# Sheet1.net
KiCad netlist of a schematic drawn in Altium Designer
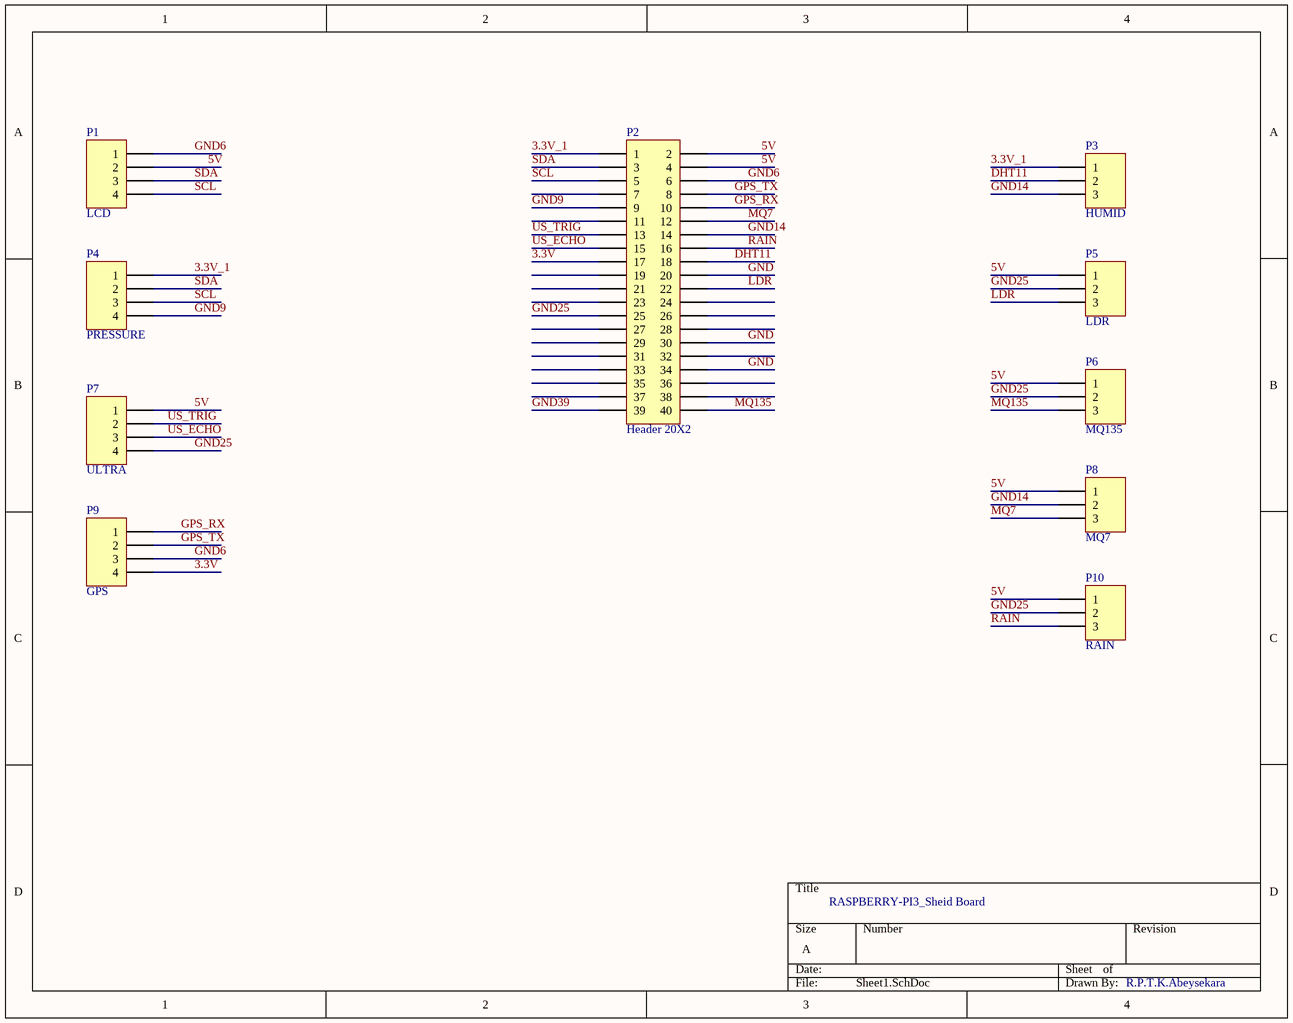
[diagram p0: Sheet1.SchDoc]

(export (version "E")
  (design (tool "Eeschema 10.0.6"))
  (components
    (comp (ref "P1")
      (value "LCD")
      (footprint "HDR1X4")
      (description "Header, 4-Pin")
      (fields (field (name "PUBLISHER") "Altium Limited"))
      (libsource (lib "Miscellaneous Connectors") (part "Header 4"))
    )
    (comp (ref "P2")
      (value "Header 20X2")
      (footprint "HDR2X20")
      (description "Header, 20-Pin, Dual row")
      (fields (field (name "PUBLISHER") "Altium Limited"))
      (libsource (lib "Miscellaneous Connectors") (part "Header 20X2"))
    )
    (comp (ref "P3")
      (value "HUMID")
      (footprint "HDR1X3")
      (description "Header, 3-Pin")
      (fields (field (name "PUBLISHER") "Altium Limited"))
      (libsource (lib "Miscellaneous Connectors") (part "Header 3"))
    )
    (comp (ref "P4")
      (value "PRESSURE")
      (footprint "HDR1X4")
      (description "Header, 4-Pin")
      (fields (field (name "PUBLISHER") "Altium Limited"))
      (libsource (lib "Miscellaneous Connectors") (part "Header 4"))
    )
    (comp (ref "P5")
      (value "LDR")
      (footprint "HDR1X3")
      (description "Header, 3-Pin")
      (fields (field (name "PUBLISHER") "Altium Limited"))
      (libsource (lib "Miscellaneous Connectors") (part "Header 3"))
    )
    (comp (ref "P6")
      (value "MQ135")
      (footprint "HDR1X3")
      (description "Header, 3-Pin")
      (fields (field (name "PUBLISHER") "Altium Limited"))
      (libsource (lib "Miscellaneous Connectors") (part "Header 3"))
    )
    (comp (ref "P7")
      (value "ULTRA")
      (footprint "HDR1X4")
      (description "Header, 4-Pin")
      (fields (field (name "PUBLISHER") "Altium Limited"))
      (libsource (lib "Miscellaneous Connectors") (part "Header 4"))
    )
    (comp (ref "P8")
      (value "MQ7")
      (footprint "HDR1X3")
      (description "Header, 3-Pin")
      (fields (field (name "PUBLISHER") "Altium Limited"))
      (libsource (lib "Miscellaneous Connectors") (part "Header 3"))
    )
    (comp (ref "P9")
      (value "GPS")
      (footprint "HDR1X4")
      (description "Header, 4-Pin")
      (fields (field (name "PUBLISHER") "Altium Limited"))
      (libsource (lib "Miscellaneous Connectors") (part "Header 4"))
    )
    (comp (ref "P10")
      (value "RAIN")
      (footprint "HDR1X3")
      (description "Header, 3-Pin")
      (fields (field (name "PUBLISHER") "Altium Limited"))
      (libsource (lib "Miscellaneous Connectors") (part "Header 3"))
    )
  )
  (nets
    (net (code "1") (name "/3.3V") (class "Default")
      (node (ref "P2") (pin "17") (pinfunction "17_17") (pintype "passive"))
      (node (ref "P9") (pin "4") (pinfunction "4_4") (pintype "passive"))
    )
    (net (code "2") (name "/3.3V_1") (class "Default")
      (node (ref "P2") (pin "1") (pinfunction "1_1") (pintype "passive"))
      (node (ref "P3") (pin "1") (pinfunction "1_1") (pintype "passive"))
      (node (ref "P4") (pin "1") (pinfunction "1_1") (pintype "passive"))
    )
    (net (code "3") (name "/5V") (class "Default")
      (node (ref "P1") (pin "2") (pinfunction "2_2") (pintype "passive"))
      (node (ref "P10") (pin "1") (pinfunction "1_1") (pintype "passive"))
      (node (ref "P2") (pin "2") (pinfunction "2_2") (pintype "passive"))
      (node (ref "P2") (pin "4") (pinfunction "4_4") (pintype "passive"))
      (node (ref "P5") (pin "1") (pinfunction "1_1") (pintype "passive"))
      (node (ref "P6") (pin "1") (pinfunction "1_1") (pintype "passive"))
      (node (ref "P7") (pin "1") (pinfunction "1_1") (pintype "passive"))
      (node (ref "P8") (pin "1") (pinfunction "1_1") (pintype "passive"))
    )
    (net (code "4") (name "/DHT11") (class "Default")
      (node (ref "P2") (pin "18") (pinfunction "18_18") (pintype "passive"))
      (node (ref "P3") (pin "2") (pinfunction "2_2") (pintype "passive"))
    )
    (net (code "5") (name "/GND") (class "Default")
      (node (ref "P2") (pin "20") (pinfunction "20_20") (pintype "passive"))
      (node (ref "P2") (pin "30") (pinfunction "30_30") (pintype "passive"))
      (node (ref "P2") (pin "34") (pinfunction "34_34") (pintype "passive"))
    )
    (net (code "6") (name "/GND6") (class "Default")
      (node (ref "P1") (pin "1") (pinfunction "1_1") (pintype "passive"))
      (node (ref "P2") (pin "6") (pinfunction "6_6") (pintype "passive"))
      (node (ref "P9") (pin "3") (pinfunction "3_3") (pintype "passive"))
    )
    (net (code "7") (name "/GND9") (class "Default")
      (node (ref "P2") (pin "9") (pinfunction "9_9") (pintype "passive"))
      (node (ref "P4") (pin "4") (pinfunction "4_4") (pintype "passive"))
    )
    (net (code "8") (name "/GND14") (class "Default")
      (node (ref "P2") (pin "14") (pinfunction "14_14") (pintype "passive"))
      (node (ref "P3") (pin "3") (pinfunction "3_3") (pintype "passive"))
      (node (ref "P8") (pin "2") (pinfunction "2_2") (pintype "passive"))
    )
    (net (code "9") (name "/GND25") (class "Default")
      (node (ref "P10") (pin "2") (pinfunction "2_2") (pintype "passive"))
      (node (ref "P2") (pin "25") (pinfunction "25_25") (pintype "passive"))
      (node (ref "P5") (pin "2") (pinfunction "2_2") (pintype "passive"))
      (node (ref "P6") (pin "2") (pinfunction "2_2") (pintype "passive"))
      (node (ref "P7") (pin "4") (pinfunction "4_4") (pintype "passive"))
    )
    (net (code "10") (name "/GND39") (class "Default")
      (node (ref "P2") (pin "39") (pinfunction "39_39") (pintype "passive"))
    )
    (net (code "11") (name "/GPS_RX") (class "Default")
      (node (ref "P2") (pin "10") (pinfunction "10_10") (pintype "passive"))
      (node (ref "P9") (pin "1") (pinfunction "1_1") (pintype "passive"))
    )
    (net (code "12") (name "/GPS_TX") (class "Default")
      (node (ref "P2") (pin "8") (pinfunction "8_8") (pintype "passive"))
      (node (ref "P9") (pin "2") (pinfunction "2_2") (pintype "passive"))
    )
    (net (code "13") (name "/LDR") (class "Default")
      (node (ref "P2") (pin "22") (pinfunction "22_22") (pintype "passive"))
      (node (ref "P5") (pin "3") (pinfunction "3_3") (pintype "passive"))
    )
    (net (code "14") (name "/MQ7") (class "Default")
      (node (ref "P2") (pin "12") (pinfunction "12_12") (pintype "passive"))
      (node (ref "P8") (pin "3") (pinfunction "3_3") (pintype "passive"))
    )
    (net (code "15") (name "/MQ135") (class "Default")
      (node (ref "P2") (pin "40") (pinfunction "40_40") (pintype "passive"))
      (node (ref "P6") (pin "3") (pinfunction "3_3") (pintype "passive"))
    )
    (net (code "16") (name "/RAIN") (class "Default")
      (node (ref "P10") (pin "3") (pinfunction "3_3") (pintype "passive"))
      (node (ref "P2") (pin "16") (pinfunction "16_16") (pintype "passive"))
    )
    (net (code "17") (name "/SCL") (class "Default")
      (node (ref "P1") (pin "4") (pinfunction "4_4") (pintype "passive"))
      (node (ref "P2") (pin "5") (pinfunction "5_5") (pintype "passive"))
      (node (ref "P4") (pin "3") (pinfunction "3_3") (pintype "passive"))
    )
    (net (code "18") (name "/SDA") (class "Default")
      (node (ref "P1") (pin "3") (pinfunction "3_3") (pintype "passive"))
      (node (ref "P2") (pin "3") (pinfunction "3_3") (pintype "passive"))
      (node (ref "P4") (pin "2") (pinfunction "2_2") (pintype "passive"))
    )
    (net (code "19") (name "/US_ECHO") (class "Default")
      (node (ref "P2") (pin "15") (pinfunction "15_15") (pintype "passive"))
      (node (ref "P7") (pin "3") (pinfunction "3_3") (pintype "passive"))
    )
    (net (code "20") (name "/US_TRIG") (class "Default")
      (node (ref "P2") (pin "13") (pinfunction "13_13") (pintype "passive"))
      (node (ref "P7") (pin "2") (pinfunction "2_2") (pintype "passive"))
    )
    (net (code "21") (name "unconnected-(P2-Pad7)") (class "Default")
      (node (ref "P2") (pin "7") (pinfunction "7_7") (pintype "passive"))
    )
    (net (code "22") (name "unconnected-(P2-Pad11)") (class "Default")
      (node (ref "P2") (pin "11") (pinfunction "11_11") (pintype "passive"))
    )
    (net (code "23") (name "unconnected-(P2-Pad19)") (class "Default")
      (node (ref "P2") (pin "19") (pinfunction "19_19") (pintype "passive"))
    )
    (net (code "24") (name "unconnected-(P2-Pad21)") (class "Default")
      (node (ref "P2") (pin "21") (pinfunction "21_21") (pintype "passive"))
    )
    (net (code "25") (name "unconnected-(P2-Pad23)") (class "Default")
      (node (ref "P2") (pin "23") (pinfunction "23_23") (pintype "passive"))
    )
    (net (code "26") (name "unconnected-(P2-Pad24)") (class "Default")
      (node (ref "P2") (pin "24") (pinfunction "24_24") (pintype "passive"))
    )
    (net (code "27") (name "unconnected-(P2-Pad26)") (class "Default")
      (node (ref "P2") (pin "26") (pinfunction "26_26") (pintype "passive"))
    )
    (net (code "28") (name "unconnected-(P2-Pad27)") (class "Default")
      (node (ref "P2") (pin "27") (pinfunction "27_27") (pintype "passive"))
    )
    (net (code "29") (name "unconnected-(P2-Pad28)") (class "Default")
      (node (ref "P2") (pin "28") (pinfunction "28_28") (pintype "passive"))
    )
    (net (code "30") (name "unconnected-(P2-Pad29)") (class "Default")
      (node (ref "P2") (pin "29") (pinfunction "29_29") (pintype "passive"))
    )
    (net (code "31") (name "unconnected-(P2-Pad31)") (class "Default")
      (node (ref "P2") (pin "31") (pinfunction "31_31") (pintype "passive"))
    )
    (net (code "32") (name "unconnected-(P2-Pad32)") (class "Default")
      (node (ref "P2") (pin "32") (pinfunction "32_32") (pintype "passive"))
    )
    (net (code "33") (name "unconnected-(P2-Pad33)") (class "Default")
      (node (ref "P2") (pin "33") (pinfunction "33_33") (pintype "passive"))
    )
    (net (code "34") (name "unconnected-(P2-Pad35)") (class "Default")
      (node (ref "P2") (pin "35") (pinfunction "35_35") (pintype "passive"))
    )
    (net (code "35") (name "unconnected-(P2-Pad36)") (class "Default")
      (node (ref "P2") (pin "36") (pinfunction "36_36") (pintype "passive"))
    )
    (net (code "36") (name "unconnected-(P2-Pad37)") (class "Default")
      (node (ref "P2") (pin "37") (pinfunction "37_37") (pintype "passive"))
    )
    (net (code "37") (name "unconnected-(P2-Pad38)") (class "Default")
      (node (ref "P2") (pin "38") (pinfunction "38_38") (pintype "passive"))
    )
  )
)
